# pcb_univ_3-2-_3-4_-x-rev2.net
KiCad netlist of a schematic drawn in EAGLE
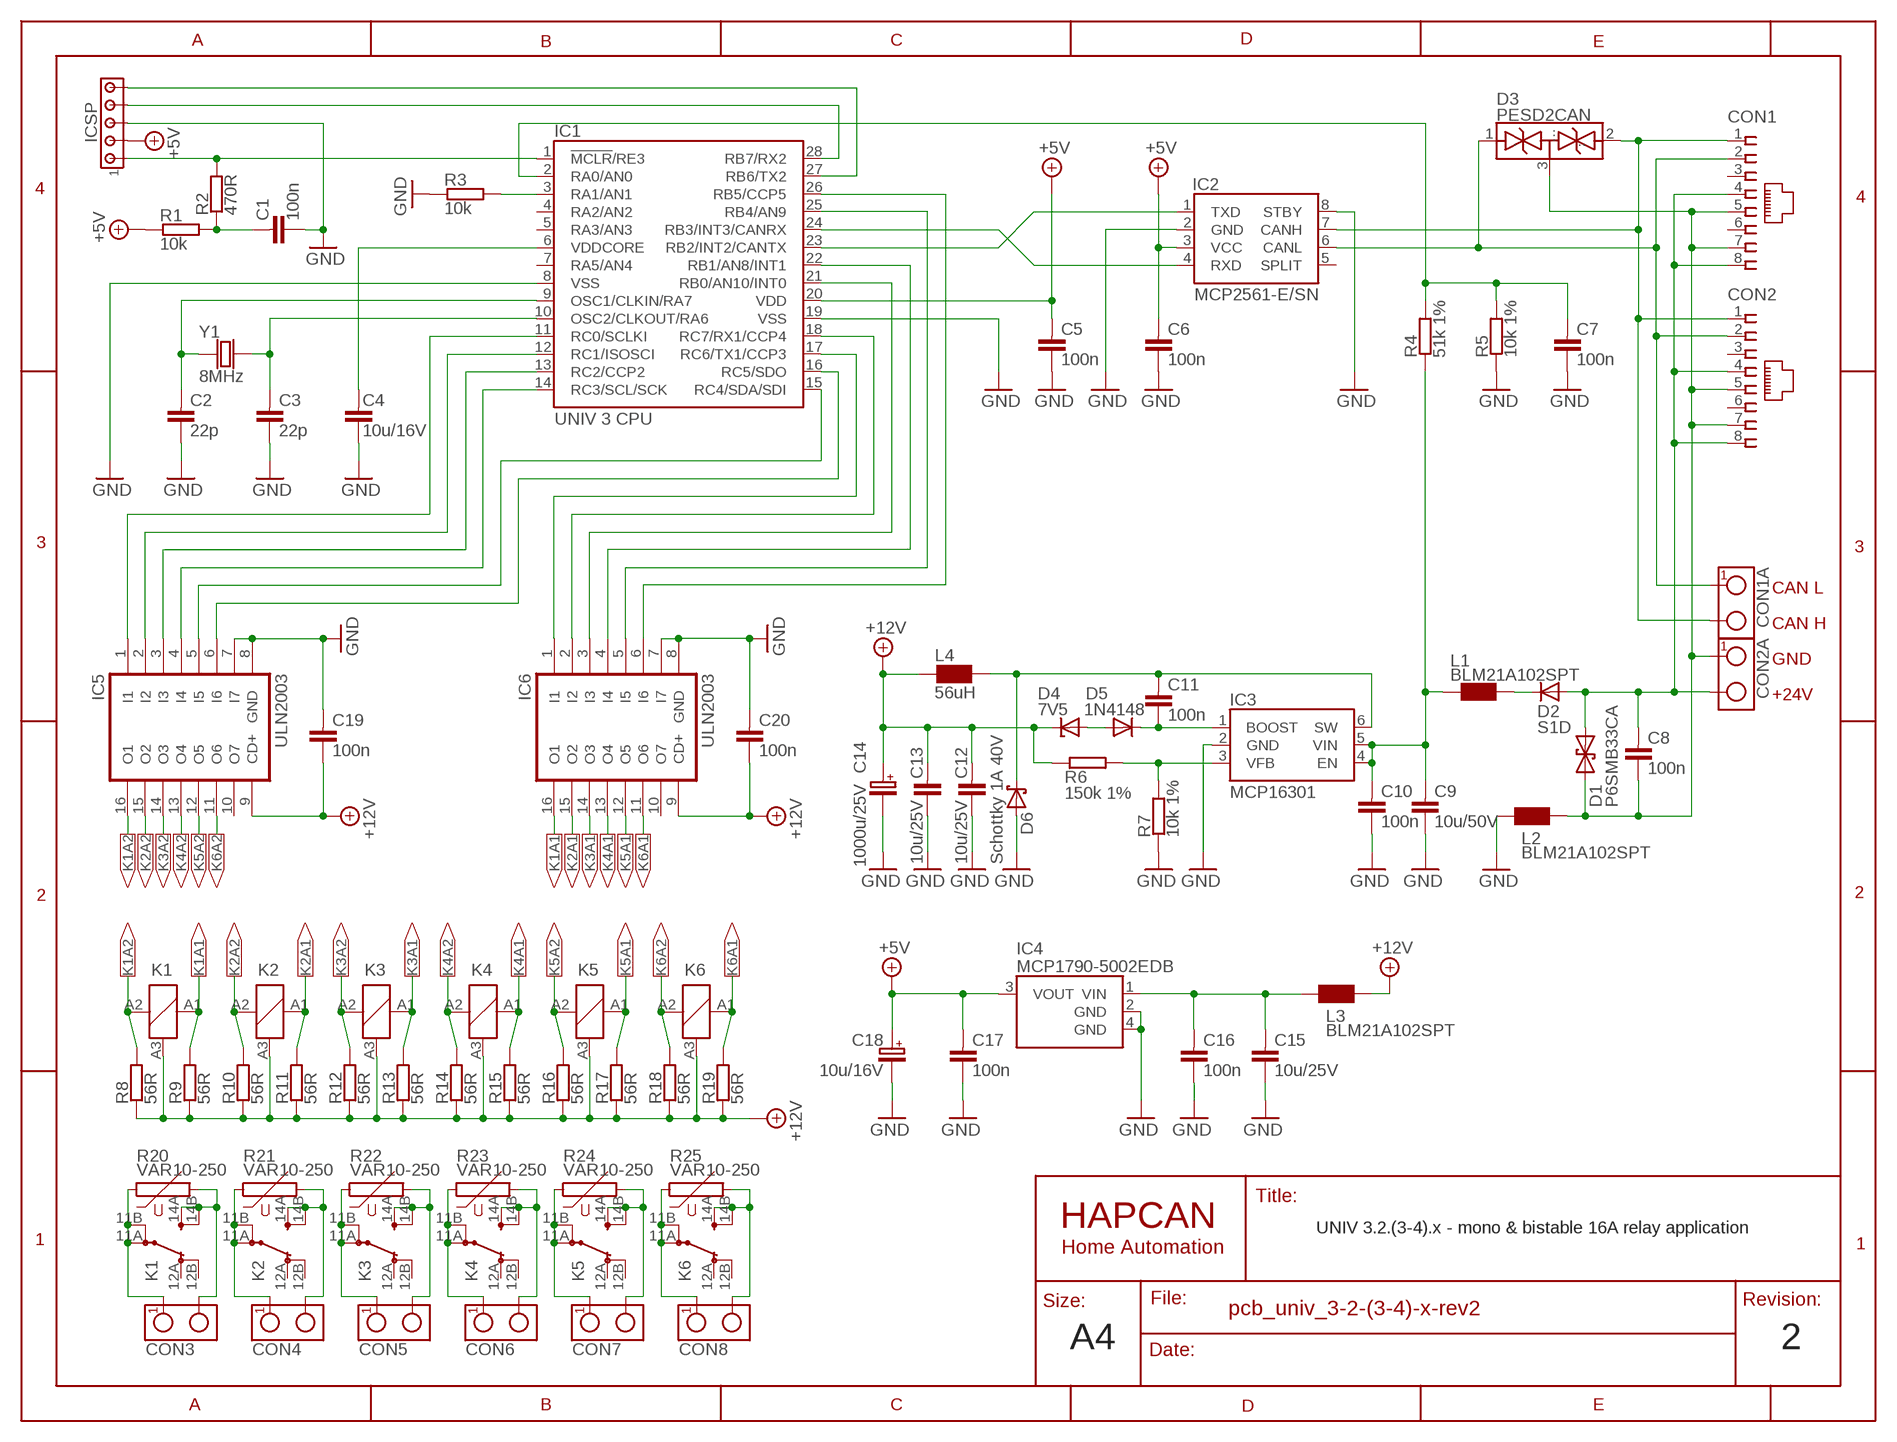
[diagram p0: schematic, sheet 1]

(export (version "E")
  (design (tool "Eeschema 10.0.6"))
  (components
    (comp (ref "C1")
      (value "100n")
      (footprint "eagle-import:0805")
      (libsource (lib "eagle-import") (part "CAPACITOR0805"))
    )
    (comp (ref "C2")
      (value "22p")
      (footprint "eagle-import:0805")
      (libsource (lib "eagle-import") (part "CAPACITOR0805"))
    )
    (comp (ref "C3")
      (value "22p")
      (footprint "eagle-import:0805")
      (libsource (lib "eagle-import") (part "CAPACITOR0805"))
    )
    (comp (ref "C4")
      (value "10u/16V")
      (footprint "eagle-import:0805")
      (libsource (lib "eagle-import") (part "CAPACITOR0805"))
    )
    (comp (ref "C5")
      (value "100n")
      (footprint "eagle-import:0805")
      (libsource (lib "eagle-import") (part "CAPACITOR0805"))
    )
    (comp (ref "C6")
      (value "100n")
      (footprint "eagle-import:0805")
      (libsource (lib "eagle-import") (part "CAPACITOR0805"))
    )
    (comp (ref "C7")
      (value "100n")
      (footprint "eagle-import:0805")
      (libsource (lib "eagle-import") (part "CAPACITOR0805"))
    )
    (comp (ref "C8")
      (value "100n")
      (footprint "eagle-import:0805")
      (libsource (lib "eagle-import") (part "CAPACITOR0805"))
    )
    (comp (ref "C9")
      (value "10u/50V")
      (footprint "eagle-import:1210")
      (libsource (lib "eagle-import") (part "CAPACITOR1210"))
    )
    (comp (ref "C10")
      (value "100n")
      (footprint "eagle-import:0805")
      (libsource (lib "eagle-import") (part "CAPACITOR0805"))
    )
    (comp (ref "C11")
      (value "100n")
      (footprint "eagle-import:0805")
      (libsource (lib "eagle-import") (part "CAPACITOR0805"))
    )
    (comp (ref "C12")
      (value "10u/25V")
      (footprint "eagle-import:1206")
      (libsource (lib "eagle-import") (part "CAPACITOR1206"))
    )
    (comp (ref "C13")
      (value "10u/25V")
      (footprint "eagle-import:1206")
      (libsource (lib "eagle-import") (part "CAPACITOR1206"))
    )
    (comp (ref "C14")
      (value "1000u/25V")
      (footprint "eagle-import:CAP-5X10.5")
      (libsource (lib "eagle-import") (part "CAPACITOR-POLARIZED-5X10.5"))
    )
    (comp (ref "C15")
      (value "10u/25V")
      (footprint "eagle-import:1206")
      (libsource (lib "eagle-import") (part "CAPACITOR1206"))
    )
    (comp (ref "C16")
      (value "100n")
      (footprint "eagle-import:0805")
      (libsource (lib "eagle-import") (part "CAPACITOR0805"))
    )
    (comp (ref "C17")
      (value "100n")
      (footprint "eagle-import:0805")
      (libsource (lib "eagle-import") (part "CAPACITOR0805"))
    )
    (comp (ref "C18")
      (value "10u/16V")
      (footprint "eagle-import:SMC_B")
      (libsource (lib "eagle-import") (part "CAPACITOR-POLARIZED-SMC_B"))
    )
    (comp (ref "C19")
      (value "100n")
      (footprint "eagle-import:0805")
      (libsource (lib "eagle-import") (part "CAPACITOR0805"))
    )
    (comp (ref "C20")
      (value "100n")
      (footprint "eagle-import:0805")
      (libsource (lib "eagle-import") (part "CAPACITOR0805"))
    )
    (comp (ref "CON1")
      (value "RJ45-SOCKET")
      (footprint "eagle-import:RJ45-PCB-SOCKET")
      (libsource (lib "eagle-import") (part "RJ45-SOCKET"))
    )
    (comp (ref "CON1A")
      (value "TERMINAL-2")
      (footprint "eagle-import:ARK2-5X10,5MM")
      (libsource (lib "eagle-import") (part "TERMINAL-2-5X10,5MM"))
    )
    (comp (ref "CON2")
      (value "RJ45-SOCKET")
      (footprint "eagle-import:RJ45-PCB-SOCKET")
      (libsource (lib "eagle-import") (part "RJ45-SOCKET"))
    )
    (comp (ref "CON2A")
      (value "TERMINAL-2")
      (footprint "eagle-import:ARK2-5X10,5MM")
      (libsource (lib "eagle-import") (part "TERMINAL-2-5X10,5MM"))
    )
    (comp (ref "CON3")
      (value "TERMINAL-2")
      (footprint "eagle-import:ARK2-7.5X10.5MM")
      (libsource (lib "eagle-import") (part "TERMINAL-2-7.5X10.5MM"))
    )
    (comp (ref "CON4")
      (value "TERMINAL-2")
      (footprint "eagle-import:ARK2-7.5X10.5MM")
      (libsource (lib "eagle-import") (part "TERMINAL-2-7.5X10.5MM"))
    )
    (comp (ref "CON5")
      (value "TERMINAL-2")
      (footprint "eagle-import:ARK2-7.5X10.5MM")
      (libsource (lib "eagle-import") (part "TERMINAL-2-7.5X10.5MM"))
    )
    (comp (ref "CON6")
      (value "TERMINAL-2")
      (footprint "eagle-import:ARK2-7.5X10.5MM")
      (libsource (lib "eagle-import") (part "TERMINAL-2-7.5X10.5MM"))
    )
    (comp (ref "CON7")
      (value "TERMINAL-2")
      (footprint "eagle-import:ARK2-7.5X10.5MM")
      (libsource (lib "eagle-import") (part "TERMINAL-2-7.5X10.5MM"))
    )
    (comp (ref "CON8")
      (value "TERMINAL-2")
      (footprint "eagle-import:ARK2-7.5X10.5MM")
      (libsource (lib "eagle-import") (part "TERMINAL-2-7.5X10.5MM"))
    )
    (comp (ref "D1")
      (value "P6SMB33CA")
      (footprint "eagle-import:DO-214_TRANSIL2")
      (libsource (lib "eagle-import") (part "DIODE_TRANSIL2"))
    )
    (comp (ref "D2")
      (value "S1D")
      (footprint "eagle-import:DO-214")
      (libsource (lib "eagle-import") (part "DIODE_DO-214"))
    )
    (comp (ref "D3")
      (value "PESD2CAN")
      (footprint "eagle-import:SOT-23")
      (libsource (lib "eagle-import") (part "PESD2CANSOT-23"))
    )
    (comp (ref "D4")
      (value "7V5")
      (footprint "eagle-import:SOD-80")
      (libsource (lib "eagle-import") (part "DIODE_ZENER_SOD-80"))
    )
    (comp (ref "D5")
      (value "1N4148")
      (footprint "eagle-import:0805")
      (libsource (lib "eagle-import") (part "DIODE_0805"))
    )
    (comp (ref "D6")
      (value "Schottky 1A 40V")
      (footprint "eagle-import:DO-214")
      (libsource (lib "eagle-import") (part "DIODE_TRANSIL1_DO214"))
    )
    (comp (ref "IC1")
      (value "UNIV 3 CPU")
      (footprint "eagle-import:UNIV3CPU")
      (libsource (lib "eagle-import") (part "UNIV3CPU-I/SO"))
    )
    (comp (ref "IC2")
      (value "MCP2561-E/SN")
      (footprint "eagle-import:SO-08")
      (libsource (lib "eagle-import") (part "MCP2561-E/SN"))
    )
    (comp (ref "IC3")
      (value "MCP16301")
      (footprint "eagle-import:SOT-23-6")
      (libsource (lib "eagle-import") (part "MCP16301SOT23-6"))
    )
    (comp (ref "IC4")
      (value "MCP1790-5002EDB")
      (footprint "eagle-import:SOT-223")
      (libsource (lib "eagle-import") (part "MCP1826SOT223-3"))
    )
    (comp (ref "IC5")
      (value "ULN2003")
      (footprint "eagle-import:SO-16")
      (libsource (lib "eagle-import") (part "ULN2003"))
    )
    (comp (ref "IC6")
      (value "ULN2003")
      (footprint "eagle-import:SO-16")
      (libsource (lib "eagle-import") (part "ULN2003"))
    )
    (comp (ref "ICSP")
      (value "HEADER5")
      (footprint "eagle-import:SIP-5")
      (libsource (lib "eagle-import") (part "HEADER5"))
    )
    (comp (ref "K1")
      (value "RELAY_RT")
      (footprint "eagle-import:RELAY_RT")
      (libsource (lib "eagle-import") (part "RELAY_RT"))
    )
    (comp (ref "K2")
      (value "RELAY_RT")
      (footprint "eagle-import:RELAY_RT")
      (libsource (lib "eagle-import") (part "RELAY_RT"))
    )
    (comp (ref "K3")
      (value "RELAY_RT")
      (footprint "eagle-import:RELAY_RT")
      (libsource (lib "eagle-import") (part "RELAY_RT"))
    )
    (comp (ref "K4")
      (value "RELAY_RT")
      (footprint "eagle-import:RELAY_RT")
      (libsource (lib "eagle-import") (part "RELAY_RT"))
    )
    (comp (ref "K5")
      (value "RELAY_RT")
      (footprint "eagle-import:RELAY_RT")
      (libsource (lib "eagle-import") (part "RELAY_RT"))
    )
    (comp (ref "K6")
      (value "RELAY_RT")
      (footprint "eagle-import:RELAY_RT")
      (libsource (lib "eagle-import") (part "RELAY_RT"))
    )
    (comp (ref "L1")
      (value "BLM21A102SPT")
      (footprint "eagle-import:0805")
      (libsource (lib "eagle-import") (part "CHOKE0805"))
    )
    (comp (ref "L2")
      (value "BLM21A102SPT")
      (footprint "eagle-import:0805")
      (libsource (lib "eagle-import") (part "CHOKE0805"))
    )
    (comp (ref "L3")
      (value "BLM21A102SPT")
      (footprint "eagle-import:0805")
      (libsource (lib "eagle-import") (part "CHOKE0805"))
    )
    (comp (ref "L4")
      (value "56uH")
      (footprint "eagle-import:CHOKE-DER0705")
      (libsource (lib "eagle-import") (part "CHOKEDER0705"))
    )
    (comp (ref "R1")
      (value "10k")
      (footprint "eagle-import:0805")
      (libsource (lib "eagle-import") (part "RESISTOR0805"))
    )
    (comp (ref "R2")
      (value "470R")
      (footprint "eagle-import:0805")
      (libsource (lib "eagle-import") (part "RESISTOR0805"))
    )
    (comp (ref "R3")
      (value "10k")
      (footprint "eagle-import:0805")
      (libsource (lib "eagle-import") (part "RESISTOR0805"))
    )
    (comp (ref "R4")
      (value "51k 1%")
      (footprint "eagle-import:0805")
      (libsource (lib "eagle-import") (part "RESISTOR0805"))
    )
    (comp (ref "R5")
      (value "10k 1%")
      (footprint "eagle-import:0805")
      (libsource (lib "eagle-import") (part "RESISTOR0805"))
    )
    (comp (ref "R6")
      (value "150k 1%")
      (footprint "eagle-import:0805")
      (libsource (lib "eagle-import") (part "RESISTOR0805"))
    )
    (comp (ref "R7")
      (value "10k 1%")
      (footprint "eagle-import:0805")
      (libsource (lib "eagle-import") (part "RESISTOR0805"))
    )
    (comp (ref "R8")
      (value "56R")
      (footprint "eagle-import:1206")
      (libsource (lib "eagle-import") (part "RESISTOR1206"))
    )
    (comp (ref "R9")
      (value "56R")
      (footprint "eagle-import:1206")
      (libsource (lib "eagle-import") (part "RESISTOR1206"))
    )
    (comp (ref "R10")
      (value "56R")
      (footprint "eagle-import:1206")
      (libsource (lib "eagle-import") (part "RESISTOR1206"))
    )
    (comp (ref "R11")
      (value "56R")
      (footprint "eagle-import:1206")
      (libsource (lib "eagle-import") (part "RESISTOR1206"))
    )
    (comp (ref "R12")
      (value "56R")
      (footprint "eagle-import:1206")
      (libsource (lib "eagle-import") (part "RESISTOR1206"))
    )
    (comp (ref "R13")
      (value "56R")
      (footprint "eagle-import:1206")
      (libsource (lib "eagle-import") (part "RESISTOR1206"))
    )
    (comp (ref "R14")
      (value "56R")
      (footprint "eagle-import:1206")
      (libsource (lib "eagle-import") (part "RESISTOR1206"))
    )
    (comp (ref "R15")
      (value "56R")
      (footprint "eagle-import:1206")
      (libsource (lib "eagle-import") (part "RESISTOR1206"))
    )
    (comp (ref "R16")
      (value "56R")
      (footprint "eagle-import:1206")
      (libsource (lib "eagle-import") (part "RESISTOR1206"))
    )
    (comp (ref "R17")
      (value "56R")
      (footprint "eagle-import:1206")
      (libsource (lib "eagle-import") (part "RESISTOR1206"))
    )
    (comp (ref "R18")
      (value "56R")
      (footprint "eagle-import:1206")
      (libsource (lib "eagle-import") (part "RESISTOR1206"))
    )
    (comp (ref "R19")
      (value "56R")
      (footprint "eagle-import:1206")
      (libsource (lib "eagle-import") (part "RESISTOR1206"))
    )
    (comp (ref "R20")
      (value "VAR10-250")
      (footprint "eagle-import:VARISTOR1")
      (libsource (lib "eagle-import") (part "VARISTOR7.5MM-1"))
    )
    (comp (ref "R21")
      (value "VAR10-250")
      (footprint "eagle-import:VARISTOR1")
      (libsource (lib "eagle-import") (part "VARISTOR7.5MM-1"))
    )
    (comp (ref "R22")
      (value "VAR10-250")
      (footprint "eagle-import:VARISTOR1")
      (libsource (lib "eagle-import") (part "VARISTOR7.5MM-1"))
    )
    (comp (ref "R23")
      (value "VAR10-250")
      (footprint "eagle-import:VARISTOR1")
      (libsource (lib "eagle-import") (part "VARISTOR7.5MM-1"))
    )
    (comp (ref "R24")
      (value "VAR10-250")
      (footprint "eagle-import:VARISTOR1")
      (libsource (lib "eagle-import") (part "VARISTOR7.5MM-1"))
    )
    (comp (ref "R25")
      (value "VAR10-250")
      (footprint "eagle-import:VARISTOR1")
      (libsource (lib "eagle-import") (part "VARISTOR7.5MM-1"))
    )
    (comp (ref "Y1")
      (value "8MHz")
      (footprint "eagle-import:CRYSTAL-HC49V")
      (libsource (lib "eagle-import") (part "CRYSTAL-HC49V"))
    )
  )
  (nets
    (net (code "1") (name "+5V") (class "Default")
      (node (ref "C17") (pin "1") (pinfunction "1_1") (pintype "passive"))
      (node (ref "C18") (pin "+") (pinfunction "1_+") (pintype "passive"))
      (node (ref "C5") (pin "1") (pinfunction "1_1") (pintype "passive"))
      (node (ref "C6") (pin "1") (pinfunction "1_1") (pintype "passive"))
      (node (ref "IC1") (pin "20") (pinfunction "VDD_20") (pintype "bidirectional"))
      (node (ref "IC2") (pin "3") (pinfunction "VCC_3") (pintype "bidirectional"))
      (node (ref "IC4") (pin "3") (pinfunction "VOUT_3") (pintype "bidirectional"))
      (node (ref "ICSP") (pin "2") (pinfunction "2_2") (pintype "passive"))
      (node (ref "R1") (pin "1") (pinfunction "1_1") (pintype "passive"))
    )
    (net (code "2") (name "+12V") (class "Default")
      (node (ref "C12") (pin "1") (pinfunction "1_1") (pintype "passive"))
      (node (ref "C13") (pin "1") (pinfunction "1_1") (pintype "passive"))
      (node (ref "C14") (pin "+") (pinfunction "1_+") (pintype "passive"))
      (node (ref "C19") (pin "2") (pinfunction "2_2") (pintype "passive"))
      (node (ref "C20") (pin "2") (pinfunction "2_2") (pintype "passive"))
      (node (ref "D4") (pin "C") (pinfunction "C_C") (pintype "passive"))
      (node (ref "IC5") (pin "9") (pinfunction "CD+_9") (pintype "passive"))
      (node (ref "IC6") (pin "9") (pinfunction "CD+_9") (pintype "passive"))
      (node (ref "K1") (pin "A3") (pinfunction "-_A3") (pintype "passive"))
      (node (ref "K2") (pin "A3") (pinfunction "-_A3") (pintype "passive"))
      (node (ref "K3") (pin "A3") (pinfunction "-_A3") (pintype "passive"))
      (node (ref "K4") (pin "A3") (pinfunction "-_A3") (pintype "passive"))
      (node (ref "K5") (pin "A3") (pinfunction "-_A3") (pintype "passive"))
      (node (ref "K6") (pin "A3") (pinfunction "-_A3") (pintype "passive"))
      (node (ref "L3") (pin "2") (pinfunction "2_2") (pintype "passive"))
      (node (ref "L4") (pin "1") (pinfunction "1_1") (pintype "passive"))
      (node (ref "R10") (pin "1") (pinfunction "1_1") (pintype "passive"))
      (node (ref "R11") (pin "1") (pinfunction "1_1") (pintype "passive"))
      (node (ref "R12") (pin "1") (pinfunction "1_1") (pintype "passive"))
      (node (ref "R13") (pin "1") (pinfunction "1_1") (pintype "passive"))
      (node (ref "R14") (pin "1") (pinfunction "1_1") (pintype "passive"))
      (node (ref "R15") (pin "1") (pinfunction "1_1") (pintype "passive"))
      (node (ref "R16") (pin "1") (pinfunction "1_1") (pintype "passive"))
      (node (ref "R17") (pin "1") (pinfunction "1_1") (pintype "passive"))
      (node (ref "R18") (pin "1") (pinfunction "1_1") (pintype "passive"))
      (node (ref "R19") (pin "1") (pinfunction "1_1") (pintype "passive"))
      (node (ref "R6") (pin "1") (pinfunction "1_1") (pintype "passive"))
      (node (ref "R8") (pin "1") (pinfunction "1_1") (pintype "passive"))
      (node (ref "R9") (pin "1") (pinfunction "1_1") (pintype "passive"))
    )
    (net (code "3") (name "/K1A1") (class "Default")
      (node (ref "IC6") (pin "16") (pinfunction "O1_16") (pintype "open_collector"))
      (node (ref "K1") (pin "A1") (pinfunction "S+_A1") (pintype "passive"))
      (node (ref "R9") (pin "2") (pinfunction "2_2") (pintype "passive"))
    )
    (net (code "4") (name "/K1A2") (class "Default")
      (node (ref "IC5") (pin "16") (pinfunction "O1_16") (pintype "open_collector"))
      (node (ref "K1") (pin "A2") (pinfunction "R+_A2") (pintype "passive"))
      (node (ref "R8") (pin "2") (pinfunction "2_2") (pintype "passive"))
    )
    (net (code "5") (name "/K2A1") (class "Default")
      (node (ref "IC6") (pin "15") (pinfunction "O2_15") (pintype "open_collector"))
      (node (ref "K2") (pin "A1") (pinfunction "S+_A1") (pintype "passive"))
      (node (ref "R11") (pin "2") (pinfunction "2_2") (pintype "passive"))
    )
    (net (code "6") (name "/K2A2") (class "Default")
      (node (ref "IC5") (pin "15") (pinfunction "O2_15") (pintype "open_collector"))
      (node (ref "K2") (pin "A2") (pinfunction "R+_A2") (pintype "passive"))
      (node (ref "R10") (pin "2") (pinfunction "2_2") (pintype "passive"))
    )
    (net (code "7") (name "/K3A1") (class "Default")
      (node (ref "IC6") (pin "14") (pinfunction "O3_14") (pintype "open_collector"))
      (node (ref "K3") (pin "A1") (pinfunction "S+_A1") (pintype "passive"))
      (node (ref "R13") (pin "2") (pinfunction "2_2") (pintype "passive"))
    )
    (net (code "8") (name "/K3A2") (class "Default")
      (node (ref "IC5") (pin "14") (pinfunction "O3_14") (pintype "open_collector"))
      (node (ref "K3") (pin "A2") (pinfunction "R+_A2") (pintype "passive"))
      (node (ref "R12") (pin "2") (pinfunction "2_2") (pintype "passive"))
    )
    (net (code "9") (name "/K4A1") (class "Default")
      (node (ref "IC6") (pin "13") (pinfunction "O4_13") (pintype "open_collector"))
      (node (ref "K4") (pin "A1") (pinfunction "S+_A1") (pintype "passive"))
      (node (ref "R15") (pin "2") (pinfunction "2_2") (pintype "passive"))
    )
    (net (code "10") (name "/K4A2") (class "Default")
      (node (ref "IC5") (pin "13") (pinfunction "O4_13") (pintype "open_collector"))
      (node (ref "K4") (pin "A2") (pinfunction "R+_A2") (pintype "passive"))
      (node (ref "R14") (pin "2") (pinfunction "2_2") (pintype "passive"))
    )
    (net (code "11") (name "/K5A1") (class "Default")
      (node (ref "IC6") (pin "12") (pinfunction "O5_12") (pintype "open_collector"))
      (node (ref "K5") (pin "A1") (pinfunction "S+_A1") (pintype "passive"))
      (node (ref "R17") (pin "2") (pinfunction "2_2") (pintype "passive"))
    )
    (net (code "12") (name "/K5A2") (class "Default")
      (node (ref "IC5") (pin "12") (pinfunction "O5_12") (pintype "open_collector"))
      (node (ref "K5") (pin "A2") (pinfunction "R+_A2") (pintype "passive"))
      (node (ref "R16") (pin "2") (pinfunction "2_2") (pintype "passive"))
    )
    (net (code "13") (name "/K6A1") (class "Default")
      (node (ref "IC6") (pin "11") (pinfunction "O6_11") (pintype "open_collector"))
      (node (ref "K6") (pin "A1") (pinfunction "S+_A1") (pintype "passive"))
      (node (ref "R19") (pin "2") (pinfunction "2_2") (pintype "passive"))
    )
    (net (code "14") (name "/K6A2") (class "Default")
      (node (ref "IC5") (pin "11") (pinfunction "O6_11") (pintype "open_collector"))
      (node (ref "K6") (pin "A2") (pinfunction "R+_A2") (pintype "passive"))
      (node (ref "R18") (pin "2") (pinfunction "2_2") (pintype "passive"))
    )
    (net (code "15") (name "GND") (class "Default")
      (node (ref "C1") (pin "2") (pinfunction "2_2") (pintype "passive"))
      (node (ref "C10") (pin "2") (pinfunction "2_2") (pintype "passive"))
      (node (ref "C12") (pin "2") (pinfunction "2_2") (pintype "passive"))
      (node (ref "C13") (pin "2") (pinfunction "2_2") (pintype "passive"))
      (node (ref "C14") (pin "-") (pinfunction "2_-") (pintype "passive"))
      (node (ref "C15") (pin "2") (pinfunction "2_2") (pintype "passive"))
      (node (ref "C16") (pin "2") (pinfunction "2_2") (pintype "passive"))
      (node (ref "C17") (pin "2") (pinfunction "2_2") (pintype "passive"))
      (node (ref "C18") (pin "-") (pinfunction "2_-") (pintype "passive"))
      (node (ref "C19") (pin "1") (pinfunction "1_1") (pintype "passive"))
      (node (ref "C2") (pin "2") (pinfunction "2_2") (pintype "passive"))
      (node (ref "C20") (pin "1") (pinfunction "1_1") (pintype "passive"))
      (node (ref "C3") (pin "2") (pinfunction "2_2") (pintype "passive"))
      (node (ref "C4") (pin "2") (pinfunction "2_2") (pintype "passive"))
      (node (ref "C5") (pin "2") (pinfunction "2_2") (pintype "passive"))
      (node (ref "C6") (pin "2") (pinfunction "2_2") (pintype "passive"))
      (node (ref "C7") (pin "2") (pinfunction "2_2") (pintype "passive"))
      (node (ref "C9") (pin "2") (pinfunction "2_2") (pintype "passive"))
      (node (ref "D6") (pin "A") (pinfunction "A_A") (pintype "passive"))
      (node (ref "IC1") (pin "19") (pinfunction "VSS_19") (pintype "bidirectional"))
      (node (ref "IC1") (pin "8") (pinfunction "VSS_8") (pintype "bidirectional"))
      (node (ref "IC2") (pin "2") (pinfunction "GND_2") (pintype "bidirectional"))
      (node (ref "IC2") (pin "8") (pinfunction "STBY_8") (pintype "bidirectional"))
      (node (ref "IC3") (pin "2") (pinfunction "GND_2") (pintype "bidirectional"))
      (node (ref "IC4") (pin "2") (pinfunction "GND_2") (pintype "bidirectional"))
      (node (ref "IC4") (pin "4") (pinfunction "GND_4") (pintype "bidirectional"))
      (node (ref "IC5") (pin "7") (pinfunction "I7_7") (pintype "input"))
      (node (ref "IC5") (pin "8") (pinfunction "GND_8") (pintype "power_in"))
      (node (ref "IC6") (pin "7") (pinfunction "I7_7") (pintype "input"))
      (node (ref "IC6") (pin "8") (pinfunction "GND_8") (pintype "power_in"))
      (node (ref "ICSP") (pin "3") (pinfunction "3_3") (pintype "passive"))
      (node (ref "L2") (pin "1") (pinfunction "1_1") (pintype "passive"))
      (node (ref "R3") (pin "1") (pinfunction "1_1") (pintype "passive"))
      (node (ref "R5") (pin "1") (pinfunction "1_1") (pintype "passive"))
      (node (ref "R7") (pin "1") (pinfunction "1_1") (pintype "passive"))
    )
    (net (code "16") (name "Net-(C1-Pad1)") (class "Default")
      (node (ref "C1") (pin "1") (pinfunction "1_1") (pintype "passive"))
      (node (ref "R1") (pin "2") (pinfunction "2_2") (pintype "passive"))
      (node (ref "R2") (pin "1") (pinfunction "1_1") (pintype "passive"))
    )
    (net (code "17") (name "Net-(D1-1)") (class "Default")
      (node (ref "C8") (pin "2") (pinfunction "2_2") (pintype "passive"))
      (node (ref "CON1") (pin "5") (pinfunction "5_5") (pintype "passive"))
      (node (ref "CON1") (pin "7") (pinfunction "7_7") (pintype "passive"))
      (node (ref "CON2") (pin "5") (pinfunction "5_5") (pintype "passive"))
      (node (ref "CON2") (pin "7") (pinfunction "7_7") (pintype "passive"))
      (node (ref "CON2A") (pin "1") (pinfunction "1_1") (pintype "passive"))
      (node (ref "D1") (pin "A") (pinfunction "1_A") (pintype "passive"))
      (node (ref "D3") (pin "3") (pinfunction "..._3") (pintype "bidirectional"))
      (node (ref "L2") (pin "2") (pinfunction "2_2") (pintype "passive"))
    )
    (net (code "18") (name "Net-(D1-2)") (class "Default")
      (node (ref "C8") (pin "1") (pinfunction "1_1") (pintype "passive"))
      (node (ref "CON1") (pin "4") (pinfunction "4_4") (pintype "passive"))
      (node (ref "CON1") (pin "8") (pinfunction "8_8") (pintype "passive"))
      (node (ref "CON2") (pin "4") (pinfunction "4_4") (pintype "passive"))
      (node (ref "CON2") (pin "8") (pinfunction "8_8") (pintype "passive"))
      (node (ref "CON2A") (pin "2") (pinfunction "2_2") (pintype "passive"))
      (node (ref "D1") (pin "C") (pinfunction "2_C") (pintype "passive"))
      (node (ref "D2") (pin "A") (pinfunction "A_A") (pintype "passive"))
    )
    (net (code "19") (name "Net-(D2-PadC)") (class "Default")
      (node (ref "D2") (pin "C") (pinfunction "C_C") (pintype "passive"))
      (node (ref "L1") (pin "2") (pinfunction "2_2") (pintype "passive"))
    )
    (net (code "20") (name "Net-(D3-.)") (class "Default")
      (node (ref "CON1") (pin "2") (pinfunction "2_2") (pintype "passive"))
      (node (ref "CON1A") (pin "1") (pinfunction "1_1") (pintype "passive"))
      (node (ref "CON2") (pin "2") (pinfunction "2_2") (pintype "passive"))
      (node (ref "D3") (pin "1") (pinfunction "._1") (pintype "bidirectional"))
      (node (ref "IC2") (pin "6") (pinfunction "CANL_6") (pintype "bidirectional"))
    )
    (net (code "21") (name "Net-(D3-..)") (class "Default")
      (node (ref "CON1") (pin "1") (pinfunction "1_1") (pintype "passive"))
      (node (ref "CON1A") (pin "2") (pinfunction "2_2") (pintype "passive"))
      (node (ref "CON2") (pin "1") (pinfunction "1_1") (pintype "passive"))
      (node (ref "D3") (pin "2") (pinfunction ".._2") (pintype "bidirectional"))
      (node (ref "IC2") (pin "7") (pinfunction "CANH_7") (pintype "bidirectional"))
    )
    (net (code "22") (name "Net-(D5-A)") (class "Default")
      (node (ref "D4") (pin "A") (pinfunction "A_A") (pintype "passive"))
      (node (ref "D5") (pin "2") (pinfunction "A_2") (pintype "passive"))
    )
    (net (code "23") (name "Net-(D5-C)") (class "Default")
      (node (ref "C11") (pin "2") (pinfunction "2_2") (pintype "passive"))
      (node (ref "D5") (pin "1") (pinfunction "C_1") (pintype "passive"))
      (node (ref "IC3") (pin "1") (pinfunction "BOOST_1") (pintype "bidirectional"))
    )
    (net (code "24") (name "Net-(IC1-OSC1{slash}CLKIN{slash}RA7)") (class "Default")
      (node (ref "C2") (pin "1") (pinfunction "1_1") (pintype "passive"))
      (node (ref "IC1") (pin "9") (pinfunction "OSC1/CLKIN/RA7_9") (pintype "bidirectional"))
      (node (ref "Y1") (pin "1") (pinfunction "1_1") (pintype "passive"))
    )
    (net (code "25") (name "Net-(IC1-OSC2{slash}CLKOUT{slash}RA6)") (class "Default")
      (node (ref "C3") (pin "1") (pinfunction "1_1") (pintype "passive"))
      (node (ref "IC1") (pin "10") (pinfunction "OSC2/CLKOUT/RA6_10") (pintype "bidirectional"))
      (node (ref "Y1") (pin "2") (pinfunction "2_2") (pintype "passive"))
    )
    (net (code "26") (name "Net-(IC1-RA0{slash}AN0)") (class "Default")
      (node (ref "C7") (pin "1") (pinfunction "1_1") (pintype "passive"))
      (node (ref "IC1") (pin "2") (pinfunction "RA0/AN0_2") (pintype "bidirectional"))
      (node (ref "R4") (pin "2") (pinfunction "2_2") (pintype "passive"))
      (node (ref "R5") (pin "2") (pinfunction "2_2") (pintype "passive"))
    )
    (net (code "27") (name "Net-(IC1-RA1{slash}AN1)") (class "Default")
      (node (ref "IC1") (pin "3") (pinfunction "RA1/AN1_3") (pintype "bidirectional"))
      (node (ref "R3") (pin "2") (pinfunction "2_2") (pintype "passive"))
    )
    (net (code "28") (name "Net-(IC1-RB0{slash}AN10{slash}INT0)") (class "Default")
      (node (ref "IC1") (pin "21") (pinfunction "RB0/AN10/INT0_21") (pintype "bidirectional"))
      (node (ref "IC6") (pin "3") (pinfunction "I3_3") (pintype "input"))
    )
    (net (code "29") (name "Net-(IC1-RB1{slash}AN8{slash}INT1)") (class "Default")
      (node (ref "IC1") (pin "22") (pinfunction "RB1/AN8/INT1_22") (pintype "bidirectional"))
      (node (ref "IC6") (pin "4") (pinfunction "I4_4") (pintype "input"))
    )
    (net (code "30") (name "Net-(IC1-RB2{slash}INT2{slash}CANTX)") (class "Default")
      (node (ref "IC1") (pin "23") (pinfunction "RB2/INT2/CANTX_23") (pintype "bidirectional"))
      (node (ref "IC2") (pin "1") (pinfunction "TXD_1") (pintype "bidirectional"))
    )
    (net (code "31") (name "Net-(IC1-RB3{slash}INT3{slash}CANRX)") (class "Default")
      (node (ref "IC1") (pin "24") (pinfunction "RB3/INT3/CANRX_24") (pintype "bidirectional"))
      (node (ref "IC2") (pin "4") (pinfunction "RXD_4") (pintype "bidirectional"))
    )
    (net (code "32") (name "Net-(IC1-RB4{slash}AN9)") (class "Default")
      (node (ref "IC1") (pin "25") (pinfunction "RB4/AN9_25") (pintype "bidirectional"))
      (node (ref "IC6") (pin "5") (pinfunction "I5_5") (pintype "input"))
    )
    (net (code "33") (name "Net-(IC1-RB5{slash}CCP5)") (class "Default")
      (node (ref "IC1") (pin "26") (pinfunction "RB5/CCP5_26") (pintype "bidirectional"))
      (node (ref "IC6") (pin "6") (pinfunction "I6_6") (pintype "input"))
    )
    (net (code "34") (name "Net-(IC1-RB6{slash}TX2)") (class "Default")
      (node (ref "IC1") (pin "27") (pinfunction "RB6/TX2_27") (pintype "bidirectional"))
      (node (ref "ICSP") (pin "5") (pinfunction "5_5") (pintype "passive"))
    )
    (net (code "35") (name "Net-(IC1-RB7{slash}RX2)") (class "Default")
      (node (ref "IC1") (pin "28") (pinfunction "RB7/RX2_28") (pintype "bidirectional"))
      (node (ref "ICSP") (pin "4") (pinfunction "4_4") (pintype "passive"))
    )
    (net (code "36") (name "Net-(IC1-RC0{slash}SCLKI)") (class "Default")
      (node (ref "IC1") (pin "11") (pinfunction "RC0/SCLKI_11") (pintype "bidirectional"))
      (node (ref "IC5") (pin "1") (pinfunction "I1_1") (pintype "input"))
    )
    (net (code "37") (name "Net-(IC1-RC1{slash}ISOSCI)") (class "Default")
      (node (ref "IC1") (pin "12") (pinfunction "RC1/ISOSCI_12") (pintype "bidirectional"))
      (node (ref "IC5") (pin "2") (pinfunction "I2_2") (pintype "input"))
    )
    (net (code "38") (name "Net-(IC1-RC2{slash}CCP2)") (class "Default")
      (node (ref "IC1") (pin "13") (pinfunction "RC2/CCP2_13") (pintype "bidirectional"))
      (node (ref "IC5") (pin "3") (pinfunction "I3_3") (pintype "input"))
    )
    (net (code "39") (name "Net-(IC1-RC3{slash}SCL{slash}SCK)") (class "Default")
      (node (ref "IC1") (pin "14") (pinfunction "RC3/SCL/SCK_14") (pintype "bidirectional"))
      (node (ref "IC5") (pin "4") (pinfunction "I4_4") (pintype "input"))
    )
    (net (code "40") (name "Net-(IC1-RC4{slash}SDA{slash}SDI)") (class "Default")
      (node (ref "IC1") (pin "15") (pinfunction "RC4/SDA/SDI_15") (pintype "bidirectional"))
      (node (ref "IC5") (pin "5") (pinfunction "I5_5") (pintype "input"))
    )
    (net (code "41") (name "Net-(IC1-RC5{slash}SDO)") (class "Default")
      (node (ref "IC1") (pin "16") (pinfunction "RC5/SDO_16") (pintype "bidirectional"))
      (node (ref "IC5") (pin "6") (pinfunction "I6_6") (pintype "input"))
    )
    (net (code "42") (name "Net-(IC1-RC6{slash}TX1{slash}CCP3)") (class "Default")
      (node (ref "IC1") (pin "17") (pinfunction "RC6/TX1/CCP3_17") (pintype "bidirectional"))
      (node (ref "IC6") (pin "1") (pinfunction "I1_1") (pintype "input"))
    )
    (net (code "43") (name "Net-(IC1-RC7{slash}RX1{slash}CCP4)") (class "Default")
      (node (ref "IC1") (pin "18") (pinfunction "RC7/RX1/CCP4_18") (pintype "bidirectional"))
      (node (ref "IC6") (pin "2") (pinfunction "I2_2") (pintype "input"))
    )
    (net (code "44") (name "Net-(IC1-VDDCORE)") (class "Default")
      (node (ref "C4") (pin "1") (pinfunction "1_1") (pintype "passive"))
      (node (ref "IC1") (pin "6") (pinfunction "VDDCORE_6") (pintype "bidirectional"))
    )
    (net (code "45") (name "Net-(IC1-~{MCLR}{slash}RE3)") (class "Default")
      (node (ref "IC1") (pin "1") (pinfunction "~{MCLR}/RE3_1") (pintype "bidirectional"))
      (node (ref "ICSP") (pin "1") (pinfunction "1_1") (pintype "passive"))
      (node (ref "R2") (pin "2") (pinfunction "2_2") (pintype "passive"))
    )
    (net (code "46") (name "Net-(IC3-EN)") (class "Default")
      (node (ref "C10") (pin "1") (pinfunction "1_1") (pintype "passive"))
      (node (ref "C9") (pin "1") (pinfunction "1_1") (pintype "passive"))
      (node (ref "IC3") (pin "4") (pinfunction "EN_4") (pintype "bidirectional"))
      (node (ref "IC3") (pin "5") (pinfunction "VIN_5") (pintype "bidirectional"))
      (node (ref "L1") (pin "1") (pinfunction "1_1") (pintype "passive"))
      (node (ref "R4") (pin "1") (pinfunction "1_1") (pintype "passive"))
    )
    (net (code "47") (name "Net-(IC3-SW)") (class "Default")
      (node (ref "C11") (pin "1") (pinfunction "1_1") (pintype "passive"))
      (node (ref "D6") (pin "C") (pinfunction "C_C") (pintype "passive"))
      (node (ref "IC3") (pin "6") (pinfunction "SW_6") (pintype "bidirectional"))
      (node (ref "L4") (pin "2") (pinfunction "2_2") (pintype "passive"))
    )
    (net (code "48") (name "Net-(IC3-VFB)") (class "Default")
      (node (ref "IC3") (pin "3") (pinfunction "VFB_3") (pintype "bidirectional"))
      (node (ref "R6") (pin "2") (pinfunction "2_2") (pintype "passive"))
      (node (ref "R7") (pin "2") (pinfunction "2_2") (pintype "passive"))
    )
    (net (code "49") (name "Net-(IC4-VIN)") (class "Default")
      (node (ref "C15") (pin "1") (pinfunction "1_1") (pintype "passive"))
      (node (ref "C16") (pin "1") (pinfunction "1_1") (pintype "passive"))
      (node (ref "IC4") (pin "1") (pinfunction "VIN_1") (pintype "bidirectional"))
      (node (ref "L3") (pin "1") (pinfunction "1_1") (pintype "passive"))
    )
    (net (code "50") (name "Net-(K1A-PA)") (class "Default")
      (node (ref "CON3") (pin "1") (pinfunction "1_1") (pintype "passive"))
      (node (ref "K1") (pin "11A") (pinfunction "PA_11A") (pintype "passive"))
      (node (ref "K1") (pin "11B") (pinfunction "PB_11B") (pintype "passive"))
      (node (ref "R20") (pin "1") (pinfunction "1_1") (pintype "passive"))
    )
    (net (code "51") (name "Net-(K1A-SA)") (class "Default")
      (node (ref "CON3") (pin "2") (pinfunction "2_2") (pintype "passive"))
      (node (ref "K1") (pin "14A") (pinfunction "SA_14A") (pintype "passive"))
      (node (ref "K1") (pin "14B") (pinfunction "SB_14B") (pintype "passive"))
      (node (ref "R20") (pin "2") (pinfunction "2_2") (pintype "passive"))
    )
    (net (code "52") (name "Net-(K2A-PA)") (class "Default")
      (node (ref "CON4") (pin "1") (pinfunction "1_1") (pintype "passive"))
      (node (ref "K2") (pin "11A") (pinfunction "PA_11A") (pintype "passive"))
      (node (ref "K2") (pin "11B") (pinfunction "PB_11B") (pintype "passive"))
      (node (ref "R21") (pin "1") (pinfunction "1_1") (pintype "passive"))
    )
    (net (code "53") (name "Net-(K2A-SA)") (class "Default")
      (node (ref "CON4") (pin "2") (pinfunction "2_2") (pintype "passive"))
      (node (ref "K2") (pin "14A") (pinfunction "SA_14A") (pintype "passive"))
      (node (ref "K2") (pin "14B") (pinfunction "SB_14B") (pintype "passive"))
      (node (ref "R21") (pin "2") (pinfunction "2_2") (pintype "passive"))
    )
    (net (code "54") (name "Net-(K3A-PA)") (class "Default")
      (node (ref "CON5") (pin "1") (pinfunction "1_1") (pintype "passive"))
      (node (ref "K3") (pin "11A") (pinfunction "PA_11A") (pintype "passive"))
      (node (ref "K3") (pin "11B") (pinfunction "PB_11B") (pintype "passive"))
      (node (ref "R22") (pin "1") (pinfunction "1_1") (pintype "passive"))
    )
    (net (code "55") (name "Net-(K3A-SA)") (class "Default")
      (node (ref "CON5") (pin "2") (pinfunction "2_2") (pintype "passive"))
      (node (ref "K3") (pin "14A") (pinfunction "SA_14A") (pintype "passive"))
      (node (ref "K3") (pin "14B") (pinfunction "SB_14B") (pintype "passive"))
      (node (ref "R22") (pin "2") (pinfunction "2_2") (pintype "passive"))
    )
    (net (code "56") (name "Net-(K4A-PA)") (class "Default")
      (node (ref "CON6") (pin "1") (pinfunction "1_1") (pintype "passive"))
      (node (ref "K4") (pin "11A") (pinfunction "PA_11A") (pintype "passive"))
      (node (ref "K4") (pin "11B") (pinfunction "PB_11B") (pintype "passive"))
      (node (ref "R23") (pin "1") (pinfunction "1_1") (pintype "passive"))
    )
    (net (code "57") (name "Net-(K4A-SA)") (class "Default")
      (node (ref "CON6") (pin "2") (pinfunction "2_2") (pintype "passive"))
      (node (ref "K4") (pin "14A") (pinfunction "SA_14A") (pintype "passive"))
      (node (ref "K4") (pin "14B") (pinfunction "SB_14B") (pintype "passive"))
      (node (ref "R23") (pin "2") (pinfunction "2_2") (pintype "passive"))
    )
    (net (code "58") (name "Net-(K5A-PA)") (class "Default")
      (node (ref "CON7") (pin "1") (pinfunction "1_1") (pintype "passive"))
      (node (ref "K5") (pin "11A") (pinfunction "PA_11A") (pintype "passive"))
      (node (ref "K5") (pin "11B") (pinfunction "PB_11B") (pintype "passive"))
      (node (ref "R24") (pin "1") (pinfunction "1_1") (pintype "passive"))
    )
    (net (code "59") (name "Net-(K5A-SA)") (class "Default")
      (node (ref "CON7") (pin "2") (pinfunction "2_2") (pintype "passive"))
      (node (ref "K5") (pin "14A") (pinfunction "SA_14A") (pintype "passive"))
      (node (ref "K5") (pin "14B") (pinfunction "SB_14B") (pintype "passive"))
      (node (ref "R24") (pin "2") (pinfunction "2_2") (pintype "passive"))
    )
    (net (code "60") (name "Net-(K6A-PA)") (class "Default")
      (node (ref "CON8") (pin "1") (pinfunction "1_1") (pintype "passive"))
      (node (ref "K6") (pin "11A") (pinfunction "PA_11A") (pintype "passive"))
      (node (ref "K6") (pin "11B") (pinfunction "PB_11B") (pintype "passive"))
      (node (ref "R25") (pin "1") (pinfunction "1_1") (pintype "passive"))
    )
    (net (code "61") (name "Net-(K6A-SA)") (class "Default")
      (node (ref "CON8") (pin "2") (pinfunction "2_2") (pintype "passive"))
      (node (ref "K6") (pin "14A") (pinfunction "SA_14A") (pintype "passive"))
      (node (ref "K6") (pin "14B") (pinfunction "SB_14B") (pintype "passive"))
      (node (ref "R25") (pin "2") (pinfunction "2_2") (pintype "passive"))
    )
    (net (code "62") (name "unconnected-(CON1-Pad3)") (class "Default")
      (node (ref "CON1") (pin "3") (pinfunction "3_3") (pintype "passive"))
    )
    (net (code "63") (name "unconnected-(CON1-Pad6)") (class "Default")
      (node (ref "CON1") (pin "6") (pinfunction "6_6") (pintype "passive"))
    )
    (net (code "64") (name "unconnected-(CON2-Pad3)") (class "Default")
      (node (ref "CON2") (pin "3") (pinfunction "3_3") (pintype "passive"))
    )
    (net (code "65") (name "unconnected-(CON2-Pad6)") (class "Default")
      (node (ref "CON2") (pin "6") (pinfunction "6_6") (pintype "passive"))
    )
    (net (code "66") (name "unconnected-(IC1-RA2{slash}AN2-Pad4)") (class "Default")
      (node (ref "IC1") (pin "4") (pinfunction "RA2/AN2_4") (pintype "bidirectional"))
    )
    (net (code "67") (name "unconnected-(IC1-RA3{slash}AN3-Pad5)") (class "Default")
      (node (ref "IC1") (pin "5") (pinfunction "RA3/AN3_5") (pintype "bidirectional"))
    )
    (net (code "68") (name "unconnected-(IC1-RA5{slash}AN4-Pad7)") (class "Default")
      (node (ref "IC1") (pin "7") (pinfunction "RA5/AN4_7") (pintype "bidirectional"))
    )
    (net (code "69") (name "unconnected-(IC2-SPLIT-Pad5)") (class "Default")
      (node (ref "IC2") (pin "5") (pinfunction "SPLIT_5") (pintype "bidirectional"))
    )
    (net (code "70") (name "unconnected-(IC5-O7-Pad10)") (class "Default")
      (node (ref "IC5") (pin "10") (pinfunction "O7_10") (pintype "open_collector"))
    )
    (net (code "71") (name "unconnected-(IC6-O7-Pad10)") (class "Default")
      (node (ref "IC6") (pin "10") (pinfunction "O7_10") (pintype "open_collector"))
    )
    (net (code "72") (name "unconnected-(K1A-OA-Pad12A)") (class "Default")
      (node (ref "K1") (pin "12A") (pinfunction "OA_12A") (pintype "passive"))
    )
    (net (code "73") (name "unconnected-(K1A-OB-Pad12B)") (class "Default")
      (node (ref "K1") (pin "12B") (pinfunction "OB_12B") (pintype "passive"))
    )
    (net (code "74") (name "unconnected-(K2A-OA-Pad12A)") (class "Default")
      (node (ref "K2") (pin "12A") (pinfunction "OA_12A") (pintype "passive"))
    )
    (net (code "75") (name "unconnected-(K2A-OB-Pad12B)") (class "Default")
      (node (ref "K2") (pin "12B") (pinfunction "OB_12B") (pintype "passive"))
    )
    (net (code "76") (name "unconnected-(K3A-OA-Pad12A)") (class "Default")
      (node (ref "K3") (pin "12A") (pinfunction "OA_12A") (pintype "passive"))
    )
    (net (code "77") (name "unconnected-(K3A-OB-Pad12B)") (class "Default")
      (node (ref "K3") (pin "12B") (pinfunction "OB_12B") (pintype "passive"))
    )
    (net (code "78") (name "unconnected-(K4A-OA-Pad12A)") (class "Default")
      (node (ref "K4") (pin "12A") (pinfunction "OA_12A") (pintype "passive"))
    )
    (net (code "79") (name "unconnected-(K4A-OB-Pad12B)") (class "Default")
      (node (ref "K4") (pin "12B") (pinfunction "OB_12B") (pintype "passive"))
    )
    (net (code "80") (name "unconnected-(K5A-OA-Pad12A)") (class "Default")
      (node (ref "K5") (pin "12A") (pinfunction "OA_12A") (pintype "passive"))
    )
    (net (code "81") (name "unconnected-(K5A-OB-Pad12B)") (class "Default")
      (node (ref "K5") (pin "12B") (pinfunction "OB_12B") (pintype "passive"))
    )
    (net (code "82") (name "unconnected-(K6A-OA-Pad12A)") (class "Default")
      (node (ref "K6") (pin "12A") (pinfunction "OA_12A") (pintype "passive"))
    )
    (net (code "83") (name "unconnected-(K6A-OB-Pad12B)") (class "Default")
      (node (ref "K6") (pin "12B") (pinfunction "OB_12B") (pintype "passive"))
    )
  )
)
